# DRLDelay.net
KiCad netlist of a schematic drawn in Altium Designer
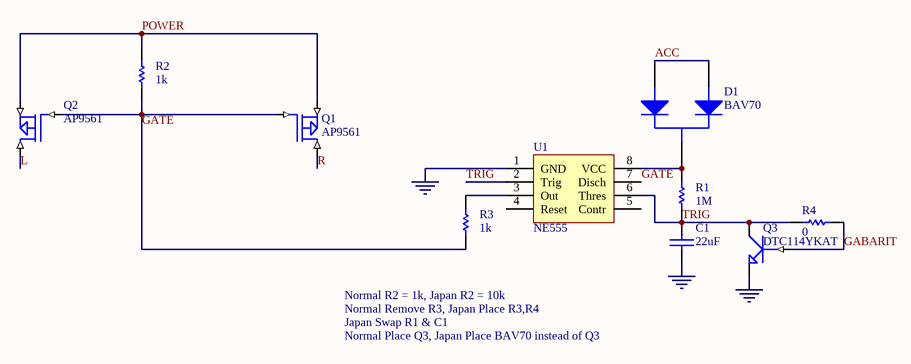
[diagram p0: DRLDelay.SchDoc]

(export (version "E")
  (design (tool "Eeschema 10.0.6"))
  (components
    (comp (ref "C1")
      (value "22uF")
      (footprint "0805")
      (description "Capacitor")
      (libsource (lib "*") (part "CAP"))
    )
    (comp (ref "D1")
      (value "BAV70")
      (footprint "SOT-23")
      (libsource (lib "Devices") (part "DUAL DIODE BAV70"))
    )
    (comp (ref "Q1") (value "AP9561") (footprint "D-Pack") (libsource (lib "*") (part "MOSFET P")))
    (comp (ref "Q2") (value "AP9561") (footprint "D-Pack") (libsource (lib "*") (part "MOSFET P")))
    (comp (ref "Q3")
      (value "DTC114YKAT")
      (footprint "SOT-23")
      (description "NPN Transistor")
      (libsource (lib "Miscellaneous Devices") (part "NPN1"))
    )
    (comp (ref "R1")
      (value "1M")
      (footprint "0805")
      (description "Resistor")
      (fields
        (field (name "MANUFACTURER") "Generic Components")
        (field (name "PUBLISHER") "Altium Hobart Technology Centre")
      )
      (libsource (lib "Miscellaneous Devices") (part "Res1"))
    )
    (comp (ref "R2")
      (value "1k")
      (footprint "1206")
      (description "Resistor")
      (fields
        (field (name "MANUFACTURER") "Generic Components")
        (field (name "PUBLISHER") "Altium Hobart Technology Centre")
      )
      (libsource (lib "Miscellaneous Devices") (part "Res1"))
    )
    (comp (ref "R3")
      (value "1k")
      (footprint "0805")
      (description "Resistor")
      (fields
        (field (name "MANUFACTURER") "Generic Components")
        (field (name "PUBLISHER") "Altium Hobart Technology Centre")
      )
      (libsource (lib "Miscellaneous Devices") (part "Res1"))
    )
    (comp (ref "R4")
      (value "0")
      (footprint "0805")
      (description "Resistor")
      (fields
        (field (name "MANUFACTURER") "Generic Components")
        (field (name "PUBLISHER") "Altium Hobart Technology Centre")
      )
      (libsource (lib "Miscellaneous Devices") (part "Res1"))
    )
    (comp (ref "U1")
      (value "NE555")
      (footprint "SO-8")
      (description "Timer 555")
      (libsource (lib "Devices") (part "NE555"))
    )
  )
  (nets
    (net (code "1") (name "/ACC") (class "Default")
      (node (ref "D1") (pin "1") (pinfunction "A1_1") (pintype "passive"))
      (node (ref "D1") (pin "3") (pinfunction "A2_3") (pintype "passive"))
    )
    (net (code "2") (name "/GABARIT") (class "Default")
      (node (ref "Q3") (pin "1") (pinfunction "B_1") (pintype "input"))
      (node (ref "R4") (pin "1") (pinfunction "1_1") (pintype "passive"))
    )
    (net (code "3") (name "/GATE") (class "Default")
      (node (ref "Q1") (pin "1") (pinfunction "GATE_1") (pintype "input"))
      (node (ref "Q2") (pin "1") (pinfunction "GATE_1") (pintype "input"))
      (node (ref "R2") (pin "2") (pinfunction "2_2") (pintype "passive"))
      (node (ref "R3") (pin "2") (pinfunction "2_2") (pintype "passive"))
      (node (ref "U1") (pin "7") (pinfunction "Disch_7") (pintype "passive"))
    )
    (net (code "4") (name "/L") (class "Default")
      (node (ref "Q2") (pin "2") (pinfunction "DRAIN_2") (pintype "input"))
    )
    (net (code "5") (name "/POWER") (class "Default")
      (node (ref "Q1") (pin "3") (pinfunction "SOURCE_3") (pintype "input"))
      (node (ref "Q2") (pin "3") (pinfunction "SOURCE_3") (pintype "input"))
      (node (ref "R2") (pin "1") (pinfunction "1_1") (pintype "passive"))
    )
    (net (code "6") (name "/R") (class "Default")
      (node (ref "Q1") (pin "2") (pinfunction "DRAIN_2") (pintype "input"))
    )
    (net (code "7") (name "/TRIG") (class "Default")
      (node (ref "C1") (pin "1") (pinfunction "1_1") (pintype "passive"))
      (node (ref "Q3") (pin "2") (pinfunction "C_2") (pintype "passive"))
      (node (ref "R1") (pin "2") (pinfunction "2_2") (pintype "passive"))
      (node (ref "R4") (pin "2") (pinfunction "2_2") (pintype "passive"))
      (node (ref "U1") (pin "2") (pinfunction "Trig_2") (pintype "passive"))
      (node (ref "U1") (pin "6") (pinfunction "Thres_6") (pintype "passive"))
    )
    (net (code "8") (name "Net-(D1-K)") (class "Default")
      (node (ref "D1") (pin "2") (pinfunction "K_2") (pintype "passive"))
      (node (ref "R1") (pin "1") (pinfunction "1_1") (pintype "passive"))
      (node (ref "U1") (pin "8") (pinfunction "VCC_8") (pintype "passive"))
    )
    (net (code "9") (name "Net-(U1-Out)") (class "Default")
      (node (ref "R3") (pin "1") (pinfunction "1_1") (pintype "passive"))
      (node (ref "U1") (pin "3") (pinfunction "Out_3") (pintype "passive"))
    )
    (net (code "10") (name "PGND") (class "Default")
      (node (ref "C1") (pin "2") (pinfunction "2_2") (pintype "passive"))
      (node (ref "Q3") (pin "3") (pinfunction "E_3") (pintype "passive"))
      (node (ref "U1") (pin "1") (pinfunction "GND_1") (pintype "passive"))
    )
    (net (code "11") (name "unconnected-(U1-Contr-Pad5)") (class "Default")
      (node (ref "U1") (pin "5") (pinfunction "Contr_5") (pintype "passive"))
    )
    (net (code "12") (name "unconnected-(U1-Reset-Pad4)") (class "Default")
      (node (ref "U1") (pin "4") (pinfunction "Reset_4") (pintype "passive"))
    )
  )
)
